# myReaderB.net
KiCad netlist of a schematic drawn in EAGLE
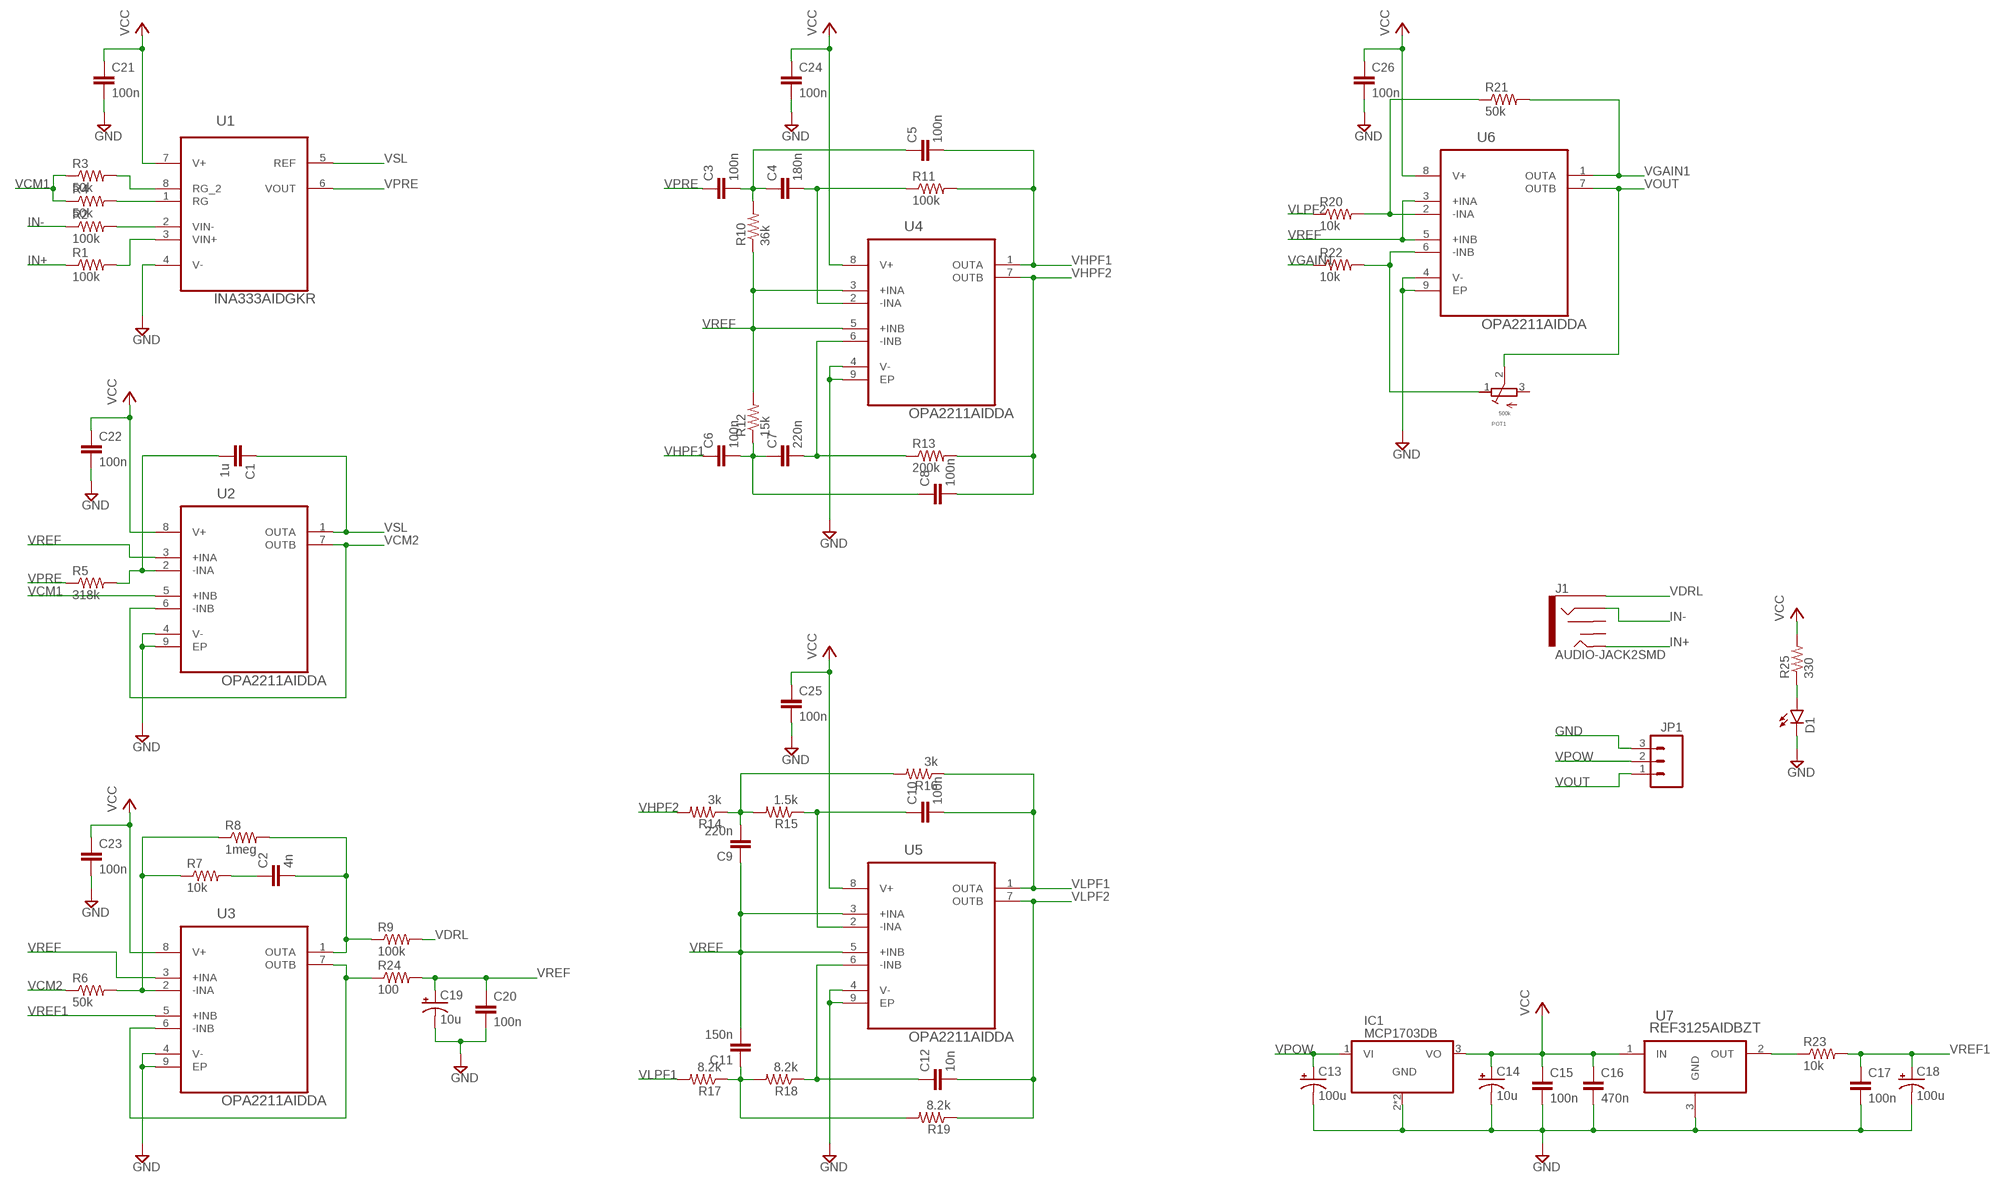
[diagram p0: schematic, sheet 1]

(export (version "E")
  (design (tool "Eeschema 10.0.6"))
  (components
    (comp (ref "C1")
      (value "1u")
      (footprint "eagle-import:0402-CAP")
      (libsource (lib "eagle-import") (part "CAP0402-CAP"))
    )
    (comp (ref "C2")
      (value "4n")
      (footprint "eagle-import:0402-CAP")
      (libsource (lib "eagle-import") (part "CAP0402-CAP"))
    )
    (comp (ref "C3")
      (value "100n")
      (footprint "eagle-import:0402-CAP")
      (libsource (lib "eagle-import") (part "CAP0402-CAP"))
    )
    (comp (ref "C4")
      (value "180n")
      (footprint "eagle-import:0402-CAP")
      (libsource (lib "eagle-import") (part "CAP0402-CAP"))
    )
    (comp (ref "C5")
      (value "100n")
      (footprint "eagle-import:0402-CAP")
      (libsource (lib "eagle-import") (part "CAP0402-CAP"))
    )
    (comp (ref "C6")
      (value "100n")
      (footprint "eagle-import:0402-CAP")
      (libsource (lib "eagle-import") (part "CAP0402-CAP"))
    )
    (comp (ref "C7")
      (value "220n")
      (footprint "eagle-import:0402-CAP")
      (libsource (lib "eagle-import") (part "CAP0402-CAP"))
    )
    (comp (ref "C8")
      (value "100n")
      (footprint "eagle-import:0402-CAP")
      (libsource (lib "eagle-import") (part "CAP0402-CAP"))
    )
    (comp (ref "C9")
      (value "220n")
      (footprint "eagle-import:0402-CAP")
      (libsource (lib "eagle-import") (part "CAP0402-CAP"))
    )
    (comp (ref "C10")
      (value "100n")
      (footprint "eagle-import:0402-CAP")
      (libsource (lib "eagle-import") (part "CAP0402-CAP"))
    )
    (comp (ref "C11")
      (value "150n")
      (footprint "eagle-import:0402-CAP")
      (libsource (lib "eagle-import") (part "CAP0402-CAP"))
    )
    (comp (ref "C12")
      (value "10n")
      (footprint "eagle-import:0402-CAP")
      (libsource (lib "eagle-import") (part "CAP0402-CAP"))
    )
    (comp (ref "C13")
      (value "100u")
      (footprint "eagle-import:EIA3216")
      (libsource (lib "eagle-import") (part "CAP_POL1206"))
    )
    (comp (ref "C14")
      (value "10u")
      (footprint "eagle-import:EIA3216")
      (libsource (lib "eagle-import") (part "CAP_POL1206"))
    )
    (comp (ref "C15")
      (value "100n")
      (footprint "eagle-import:0402-CAP")
      (libsource (lib "eagle-import") (part "CAP0402-CAP"))
    )
    (comp (ref "C16")
      (value "470n")
      (footprint "eagle-import:0402-CAP")
      (libsource (lib "eagle-import") (part "CAP0402-CAP"))
    )
    (comp (ref "C17")
      (value "100n")
      (footprint "eagle-import:0402-CAP")
      (libsource (lib "eagle-import") (part "CAP0402-CAP"))
    )
    (comp (ref "C18")
      (value "100u")
      (footprint "eagle-import:EIA3216")
      (libsource (lib "eagle-import") (part "CAP_POL1206"))
    )
    (comp (ref "C19")
      (value "10u")
      (footprint "eagle-import:EIA3216")
      (libsource (lib "eagle-import") (part "CAP_POL1206"))
    )
    (comp (ref "C20")
      (value "100n")
      (footprint "eagle-import:0402-CAP")
      (libsource (lib "eagle-import") (part "CAP0402-CAP"))
    )
    (comp (ref "C21")
      (value "100n")
      (footprint "eagle-import:0402-CAP")
      (libsource (lib "eagle-import") (part "CAP0402-CAP"))
    )
    (comp (ref "C22")
      (value "100n")
      (footprint "eagle-import:0402-CAP")
      (libsource (lib "eagle-import") (part "CAP0402-CAP"))
    )
    (comp (ref "C23")
      (value "100n")
      (footprint "eagle-import:0402-CAP")
      (libsource (lib "eagle-import") (part "CAP0402-CAP"))
    )
    (comp (ref "C24")
      (value "100n")
      (footprint "eagle-import:0402-CAP")
      (libsource (lib "eagle-import") (part "CAP0402-CAP"))
    )
    (comp (ref "C25")
      (value "100n")
      (footprint "eagle-import:0402-CAP")
      (libsource (lib "eagle-import") (part "CAP0402-CAP"))
    )
    (comp (ref "C26")
      (value "100n")
      (footprint "eagle-import:0402-CAP")
      (libsource (lib "eagle-import") (part "CAP0402-CAP"))
    )
    (comp (ref "D1")
      (value "LED0603")
      (footprint "eagle-import:LED-0603")
      (libsource (lib "eagle-import") (part "LED0603"))
    )
    (comp (ref "IC1")
      (value "MCP1703DB")
      (footprint "eagle-import:SOT223")
      (libsource (lib "eagle-import") (part "MCP1703DB"))
    )
    (comp (ref "J1")
      (value "AUDIO-JACK2SMD")
      (footprint "eagle-import:AUDIO-JACK-3.5MM-SMD")
      (libsource (lib "eagle-import") (part "AUDIO-JACK2SMD"))
    )
    (comp (ref "JP1")
      (value "M03PTH")
      (footprint "eagle-import:1X03")
      (libsource (lib "eagle-import") (part "M03PTH"))
    )
    (comp (ref "POT1")
      (value "500k")
      (footprint "eagle-import:BOURN_SMD_POTENTIOMETER")
      (libsource (lib "eagle-import") (part "BOURN_SMD_POTENTIOMETER2.1X2.7MMPACKAGE"))
    )
    (comp (ref "R1")
      (value "100k")
      (footprint "eagle-import:0402-RES")
      (libsource (lib "eagle-import") (part "RESISTOR0402-RES"))
    )
    (comp (ref "R2")
      (value "100k")
      (footprint "eagle-import:0402-RES")
      (libsource (lib "eagle-import") (part "RESISTOR0402-RES"))
    )
    (comp (ref "R3")
      (value "50k")
      (footprint "eagle-import:0402-RES")
      (libsource (lib "eagle-import") (part "RESISTOR0402-RES"))
    )
    (comp (ref "R4")
      (value "50k")
      (footprint "eagle-import:0402-RES")
      (libsource (lib "eagle-import") (part "RESISTOR0402-RES"))
    )
    (comp (ref "R5")
      (value "318k")
      (footprint "eagle-import:0402-RES")
      (libsource (lib "eagle-import") (part "RESISTOR0402-RES"))
    )
    (comp (ref "R6")
      (value "50k")
      (footprint "eagle-import:0402-RES")
      (libsource (lib "eagle-import") (part "RESISTOR0402-RES"))
    )
    (comp (ref "R7")
      (value "10k")
      (footprint "eagle-import:0402-RES")
      (libsource (lib "eagle-import") (part "RESISTOR0402-RES"))
    )
    (comp (ref "R8")
      (value "1meg")
      (footprint "eagle-import:0402-RES")
      (libsource (lib "eagle-import") (part "RESISTOR0402-RES"))
    )
    (comp (ref "R9")
      (value "100k")
      (footprint "eagle-import:0402-RES")
      (libsource (lib "eagle-import") (part "RESISTOR0402-RES"))
    )
    (comp (ref "R10")
      (value "36k")
      (footprint "eagle-import:0402-RES")
      (libsource (lib "eagle-import") (part "RESISTOR0402-RES"))
    )
    (comp (ref "R11")
      (value "100k")
      (footprint "eagle-import:0402-RES")
      (libsource (lib "eagle-import") (part "RESISTOR0402-RES"))
    )
    (comp (ref "R12")
      (value "15k")
      (footprint "eagle-import:0402-RES")
      (libsource (lib "eagle-import") (part "RESISTOR0402-RES"))
    )
    (comp (ref "R13")
      (value "200k")
      (footprint "eagle-import:0402-RES")
      (libsource (lib "eagle-import") (part "RESISTOR0402-RES"))
    )
    (comp (ref "R14")
      (value "3k")
      (footprint "eagle-import:0402-RES")
      (libsource (lib "eagle-import") (part "RESISTOR0402-RES"))
    )
    (comp (ref "R15")
      (value "1.5k")
      (footprint "eagle-import:0402-RES")
      (libsource (lib "eagle-import") (part "RESISTOR0402-RES"))
    )
    (comp (ref "R16")
      (value "3k")
      (footprint "eagle-import:0402-RES")
      (libsource (lib "eagle-import") (part "RESISTOR0402-RES"))
    )
    (comp (ref "R17")
      (value "8.2k")
      (footprint "eagle-import:0402-RES")
      (libsource (lib "eagle-import") (part "RESISTOR0402-RES"))
    )
    (comp (ref "R18")
      (value "8.2k")
      (footprint "eagle-import:0402-RES")
      (libsource (lib "eagle-import") (part "RESISTOR0402-RES"))
    )
    (comp (ref "R19")
      (value "8.2k")
      (footprint "eagle-import:0402-RES")
      (libsource (lib "eagle-import") (part "RESISTOR0402-RES"))
    )
    (comp (ref "R20")
      (value "10k")
      (footprint "eagle-import:0402-RES")
      (libsource (lib "eagle-import") (part "RESISTOR0402-RES"))
    )
    (comp (ref "R21")
      (value "50k")
      (footprint "eagle-import:0402-RES")
      (libsource (lib "eagle-import") (part "RESISTOR0402-RES"))
    )
    (comp (ref "R22")
      (value "10k")
      (footprint "eagle-import:0402-RES")
      (libsource (lib "eagle-import") (part "RESISTOR0402-RES"))
    )
    (comp (ref "R23")
      (value "10k")
      (footprint "eagle-import:0402-RES")
      (libsource (lib "eagle-import") (part "RESISTOR0402-RES"))
    )
    (comp (ref "R24")
      (value "100")
      (footprint "eagle-import:0402-RES")
      (libsource (lib "eagle-import") (part "RESISTOR0402-RES"))
    )
    (comp (ref "R25")
      (value "330")
      (footprint "eagle-import:0402-RES")
      (libsource (lib "eagle-import") (part "RESISTOR0402-RES"))
    )
    (comp (ref "U1")
      (value "INA333AIDGKR")
      (footprint "eagle-import:SOP65P490X110-8N")
      (libsource (lib "eagle-import") (part "INA333AIDGKR"))
    )
    (comp (ref "U2")
      (value "OPA2211AIDDA")
      (footprint "eagle-import:SOIC127P600X170-9N")
      (libsource (lib "eagle-import") (part "OPA2211AIDDA"))
    )
    (comp (ref "U3")
      (value "OPA2211AIDDA")
      (footprint "eagle-import:SOIC127P600X170-9N")
      (libsource (lib "eagle-import") (part "OPA2211AIDDA"))
    )
    (comp (ref "U4")
      (value "OPA2211AIDDA")
      (footprint "eagle-import:SOIC127P600X170-9N")
      (libsource (lib "eagle-import") (part "OPA2211AIDDA"))
    )
    (comp (ref "U5")
      (value "OPA2211AIDDA")
      (footprint "eagle-import:SOIC127P600X170-9N")
      (libsource (lib "eagle-import") (part "OPA2211AIDDA"))
    )
    (comp (ref "U6")
      (value "OPA2211AIDDA")
      (footprint "eagle-import:SOIC127P600X170-9N")
      (libsource (lib "eagle-import") (part "OPA2211AIDDA"))
    )
    (comp (ref "U7")
      (value "REF3125AIDBZT")
      (footprint "eagle-import:SOT95P237X112-3N")
      (libsource (lib "eagle-import") (part "REF3125AIDBZT"))
    )
  )
  (nets
    (net (code "1") (name "/IN+") (class "Default")
      (node (ref "J1") (pin "TIP") (pinfunction "TIP_TIP") (pintype "bidirectional"))
      (node (ref "R1") (pin "1") (pinfunction "1_1") (pintype "passive"))
    )
    (net (code "2") (name "/IN-") (class "Default")
      (node (ref "J1") (pin "RING") (pinfunction "RING_RING") (pintype "bidirectional"))
      (node (ref "R2") (pin "1") (pinfunction "1_1") (pintype "passive"))
    )
    (net (code "3") (name "/VCM1") (class "Default")
      (node (ref "R3") (pin "1") (pinfunction "1_1") (pintype "passive"))
      (node (ref "R4") (pin "1") (pinfunction "1_1") (pintype "passive"))
      (node (ref "U2") (pin "5") (pinfunction "+INB_5") (pintype "input"))
    )
    (net (code "4") (name "/VCM2") (class "Default")
      (node (ref "R6") (pin "1") (pinfunction "1_1") (pintype "passive"))
      (node (ref "U2") (pin "6") (pinfunction "-INB_6") (pintype "input"))
      (node (ref "U2") (pin "7") (pinfunction "OUTB_7") (pintype "output"))
    )
    (net (code "5") (name "/VDRL") (class "Default")
      (node (ref "J1") (pin "SLEEVE") (pinfunction "SLEEVE_SLEEVE") (pintype "bidirectional"))
      (node (ref "R9") (pin "2") (pinfunction "2_2") (pintype "passive"))
    )
    (net (code "6") (name "/VGAIN1") (class "Default")
      (node (ref "R21") (pin "2") (pinfunction "2_2") (pintype "passive"))
      (node (ref "R22") (pin "1") (pinfunction "1_1") (pintype "passive"))
      (node (ref "U6") (pin "1") (pinfunction "OUTA_1") (pintype "output"))
    )
    (net (code "7") (name "/VHPF1") (class "Default")
      (node (ref "C5") (pin "2") (pinfunction "2_2") (pintype "passive"))
      (node (ref "C6") (pin "1") (pinfunction "1_1") (pintype "passive"))
      (node (ref "R11") (pin "2") (pinfunction "2_2") (pintype "passive"))
      (node (ref "U4") (pin "1") (pinfunction "OUTA_1") (pintype "output"))
    )
    (net (code "8") (name "/VHPF2") (class "Default")
      (node (ref "C8") (pin "2") (pinfunction "2_2") (pintype "passive"))
      (node (ref "R13") (pin "2") (pinfunction "2_2") (pintype "passive"))
      (node (ref "R14") (pin "2") (pinfunction "2_2") (pintype "passive"))
      (node (ref "U4") (pin "7") (pinfunction "OUTB_7") (pintype "output"))
    )
    (net (code "9") (name "/VLPF1") (class "Default")
      (node (ref "C10") (pin "2") (pinfunction "2_2") (pintype "passive"))
      (node (ref "R16") (pin "1") (pinfunction "1_1") (pintype "passive"))
      (node (ref "R17") (pin "2") (pinfunction "2_2") (pintype "passive"))
      (node (ref "U5") (pin "1") (pinfunction "OUTA_1") (pintype "output"))
    )
    (net (code "10") (name "/VLPF2") (class "Default")
      (node (ref "C12") (pin "2") (pinfunction "2_2") (pintype "passive"))
      (node (ref "R19") (pin "1") (pinfunction "1_1") (pintype "passive"))
      (node (ref "R20") (pin "1") (pinfunction "1_1") (pintype "passive"))
      (node (ref "U5") (pin "7") (pinfunction "OUTB_7") (pintype "output"))
    )
    (net (code "11") (name "/VOUT") (class "Default")
      (node (ref "JP1") (pin "1") (pinfunction "1_1") (pintype "passive"))
      (node (ref "POT1") (pin "2") (pinfunction "S_2") (pintype "passive"))
      (node (ref "U6") (pin "7") (pinfunction "OUTB_7") (pintype "output"))
    )
    (net (code "12") (name "/VPOW") (class "Default")
      (node (ref "C13") (pin "A") (pinfunction "+_A") (pintype "passive"))
      (node (ref "IC1") (pin "1") (pinfunction "VI_1") (pintype "input"))
      (node (ref "JP1") (pin "2") (pinfunction "2_2") (pintype "passive"))
    )
    (net (code "13") (name "/VPRE") (class "Default")
      (node (ref "C3") (pin "1") (pinfunction "1_1") (pintype "passive"))
      (node (ref "R5") (pin "1") (pinfunction "1_1") (pintype "passive"))
      (node (ref "U1") (pin "6") (pinfunction "VOUT_6") (pintype "output"))
    )
    (net (code "14") (name "/VREF") (class "Default")
      (node (ref "C11") (pin "2") (pinfunction "2_2") (pintype "passive"))
      (node (ref "C19") (pin "A") (pinfunction "+_A") (pintype "passive"))
      (node (ref "C20") (pin "1") (pinfunction "1_1") (pintype "passive"))
      (node (ref "C9") (pin "1") (pinfunction "1_1") (pintype "passive"))
      (node (ref "R10") (pin "1") (pinfunction "1_1") (pintype "passive"))
      (node (ref "R12") (pin "2") (pinfunction "2_2") (pintype "passive"))
      (node (ref "R24") (pin "2") (pinfunction "2_2") (pintype "passive"))
      (node (ref "U2") (pin "3") (pinfunction "+INA_3") (pintype "input"))
      (node (ref "U3") (pin "3") (pinfunction "+INA_3") (pintype "input"))
      (node (ref "U4") (pin "3") (pinfunction "+INA_3") (pintype "input"))
      (node (ref "U4") (pin "5") (pinfunction "+INB_5") (pintype "input"))
      (node (ref "U5") (pin "3") (pinfunction "+INA_3") (pintype "input"))
      (node (ref "U5") (pin "5") (pinfunction "+INB_5") (pintype "input"))
      (node (ref "U6") (pin "3") (pinfunction "+INA_3") (pintype "input"))
      (node (ref "U6") (pin "5") (pinfunction "+INB_5") (pintype "input"))
    )
    (net (code "15") (name "/VREF1") (class "Default")
      (node (ref "C17") (pin "1") (pinfunction "1_1") (pintype "passive"))
      (node (ref "C18") (pin "A") (pinfunction "+_A") (pintype "passive"))
      (node (ref "R23") (pin "2") (pinfunction "2_2") (pintype "passive"))
      (node (ref "U3") (pin "5") (pinfunction "+INB_5") (pintype "input"))
    )
    (net (code "16") (name "/VSL") (class "Default")
      (node (ref "C1") (pin "1") (pinfunction "1_1") (pintype "passive"))
      (node (ref "U1") (pin "5") (pinfunction "REF_5") (pintype "output"))
      (node (ref "U2") (pin "1") (pinfunction "OUTA_1") (pintype "output"))
    )
    (net (code "17") (name "GND") (class "Default")
      (node (ref "C13") (pin "C") (pinfunction "-_C") (pintype "passive"))
      (node (ref "C14") (pin "C") (pinfunction "-_C") (pintype "passive"))
      (node (ref "C15") (pin "2") (pinfunction "2_2") (pintype "passive"))
      (node (ref "C16") (pin "2") (pinfunction "2_2") (pintype "passive"))
      (node (ref "C17") (pin "2") (pinfunction "2_2") (pintype "passive"))
      (node (ref "C18") (pin "C") (pinfunction "-_C") (pintype "passive"))
      (node (ref "C19") (pin "C") (pinfunction "-_C") (pintype "passive"))
      (node (ref "C20") (pin "2") (pinfunction "2_2") (pintype "passive"))
      (node (ref "C21") (pin "2") (pinfunction "2_2") (pintype "passive"))
      (node (ref "C22") (pin "2") (pinfunction "2_2") (pintype "passive"))
      (node (ref "C23") (pin "2") (pinfunction "2_2") (pintype "passive"))
      (node (ref "C24") (pin "2") (pinfunction "2_2") (pintype "passive"))
      (node (ref "C25") (pin "2") (pinfunction "2_2") (pintype "passive"))
      (node (ref "C26") (pin "2") (pinfunction "2_2") (pintype "passive"))
      (node (ref "D1") (pin "C") (pinfunction "C_C") (pintype "passive"))
      (node (ref "IC1") (pin "2") (pinfunction "GND_2") (pintype "passive"))
      (node (ref "IC1") (pin "4") (pinfunction "GND_4") (pintype "passive"))
      (node (ref "JP1") (pin "3") (pinfunction "3_3") (pintype "passive"))
      (node (ref "U1") (pin "4") (pinfunction "V-_4") (pintype "power_in"))
      (node (ref "U2") (pin "4") (pinfunction "V-_4") (pintype "power_in"))
      (node (ref "U2") (pin "9") (pinfunction "EP_9") (pintype "power_in"))
      (node (ref "U3") (pin "4") (pinfunction "V-_4") (pintype "power_in"))
      (node (ref "U3") (pin "9") (pinfunction "EP_9") (pintype "power_in"))
      (node (ref "U4") (pin "4") (pinfunction "V-_4") (pintype "power_in"))
      (node (ref "U4") (pin "9") (pinfunction "EP_9") (pintype "power_in"))
      (node (ref "U5") (pin "4") (pinfunction "V-_4") (pintype "power_in"))
      (node (ref "U5") (pin "9") (pinfunction "EP_9") (pintype "power_in"))
      (node (ref "U6") (pin "4") (pinfunction "V-_4") (pintype "power_in"))
      (node (ref "U6") (pin "9") (pinfunction "EP_9") (pintype "power_in"))
      (node (ref "U7") (pin "3") (pinfunction "GND_3") (pintype "passive"))
    )
    (net (code "18") (name "Net-(C2-Pad1)") (class "Default")
      (node (ref "C2") (pin "1") (pinfunction "1_1") (pintype "passive"))
      (node (ref "R7") (pin "2") (pinfunction "2_2") (pintype "passive"))
    )
    (net (code "19") (name "Net-(C3-Pad2)") (class "Default")
      (node (ref "C3") (pin "2") (pinfunction "2_2") (pintype "passive"))
      (node (ref "C4") (pin "1") (pinfunction "1_1") (pintype "passive"))
      (node (ref "C5") (pin "1") (pinfunction "1_1") (pintype "passive"))
      (node (ref "R10") (pin "2") (pinfunction "2_2") (pintype "passive"))
    )
    (net (code "20") (name "Net-(C6-Pad2)") (class "Default")
      (node (ref "C6") (pin "2") (pinfunction "2_2") (pintype "passive"))
      (node (ref "C7") (pin "1") (pinfunction "1_1") (pintype "passive"))
      (node (ref "C8") (pin "1") (pinfunction "1_1") (pintype "passive"))
      (node (ref "R12") (pin "1") (pinfunction "1_1") (pintype "passive"))
    )
    (net (code "21") (name "Net-(C9-Pad2)") (class "Default")
      (node (ref "C9") (pin "2") (pinfunction "2_2") (pintype "passive"))
      (node (ref "R14") (pin "1") (pinfunction "1_1") (pintype "passive"))
      (node (ref "R15") (pin "2") (pinfunction "2_2") (pintype "passive"))
      (node (ref "R16") (pin "2") (pinfunction "2_2") (pintype "passive"))
    )
    (net (code "22") (name "Net-(C11-Pad1)") (class "Default")
      (node (ref "C11") (pin "1") (pinfunction "1_1") (pintype "passive"))
      (node (ref "R17") (pin "1") (pinfunction "1_1") (pintype "passive"))
      (node (ref "R18") (pin "2") (pinfunction "2_2") (pintype "passive"))
      (node (ref "R19") (pin "2") (pinfunction "2_2") (pintype "passive"))
    )
    (net (code "23") (name "Net-(D1-PadA)") (class "Default")
      (node (ref "D1") (pin "A") (pinfunction "A_A") (pintype "passive"))
      (node (ref "R25") (pin "1") (pinfunction "1_1") (pintype "passive"))
    )
    (net (code "24") (name "Net-(POT1-A)") (class "Default")
      (node (ref "POT1") (pin "1") (pinfunction "A_1") (pintype "passive"))
      (node (ref "R22") (pin "2") (pinfunction "2_2") (pintype "passive"))
      (node (ref "U6") (pin "6") (pinfunction "-INB_6") (pintype "input"))
    )
    (net (code "25") (name "Net-(U1-RG)") (class "Default")
      (node (ref "R4") (pin "2") (pinfunction "2_2") (pintype "passive"))
      (node (ref "U1") (pin "1") (pinfunction "RG_1") (pintype "input"))
    )
    (net (code "26") (name "Net-(U1-RG_2)") (class "Default")
      (node (ref "R3") (pin "2") (pinfunction "2_2") (pintype "passive"))
      (node (ref "U1") (pin "8") (pinfunction "RG_2_8") (pintype "input"))
    )
    (net (code "27") (name "Net-(U1-VIN+)") (class "Default")
      (node (ref "R1") (pin "2") (pinfunction "2_2") (pintype "passive"))
      (node (ref "U1") (pin "3") (pinfunction "VIN+_3") (pintype "input"))
    )
    (net (code "28") (name "Net-(U1-VIN-)") (class "Default")
      (node (ref "R2") (pin "2") (pinfunction "2_2") (pintype "passive"))
      (node (ref "U1") (pin "2") (pinfunction "VIN-_2") (pintype "input"))
    )
    (net (code "29") (name "Net-(U2--INA)") (class "Default")
      (node (ref "C1") (pin "2") (pinfunction "2_2") (pintype "passive"))
      (node (ref "R5") (pin "2") (pinfunction "2_2") (pintype "passive"))
      (node (ref "U2") (pin "2") (pinfunction "-INA_2") (pintype "input"))
    )
    (net (code "30") (name "Net-(U3--INA)") (class "Default")
      (node (ref "R6") (pin "2") (pinfunction "2_2") (pintype "passive"))
      (node (ref "R7") (pin "1") (pinfunction "1_1") (pintype "passive"))
      (node (ref "R8") (pin "1") (pinfunction "1_1") (pintype "passive"))
      (node (ref "U3") (pin "2") (pinfunction "-INA_2") (pintype "input"))
    )
    (net (code "31") (name "Net-(U3--INB)") (class "Default")
      (node (ref "R24") (pin "1") (pinfunction "1_1") (pintype "passive"))
      (node (ref "U3") (pin "6") (pinfunction "-INB_6") (pintype "input"))
      (node (ref "U3") (pin "7") (pinfunction "OUTB_7") (pintype "output"))
    )
    (net (code "32") (name "Net-(U3-OUTA)") (class "Default")
      (node (ref "C2") (pin "2") (pinfunction "2_2") (pintype "passive"))
      (node (ref "R8") (pin "2") (pinfunction "2_2") (pintype "passive"))
      (node (ref "R9") (pin "1") (pinfunction "1_1") (pintype "passive"))
      (node (ref "U3") (pin "1") (pinfunction "OUTA_1") (pintype "output"))
    )
    (net (code "33") (name "Net-(U4--INA)") (class "Default")
      (node (ref "C4") (pin "2") (pinfunction "2_2") (pintype "passive"))
      (node (ref "R11") (pin "1") (pinfunction "1_1") (pintype "passive"))
      (node (ref "U4") (pin "2") (pinfunction "-INA_2") (pintype "input"))
    )
    (net (code "34") (name "Net-(U4--INB)") (class "Default")
      (node (ref "C7") (pin "2") (pinfunction "2_2") (pintype "passive"))
      (node (ref "R13") (pin "1") (pinfunction "1_1") (pintype "passive"))
      (node (ref "U4") (pin "6") (pinfunction "-INB_6") (pintype "input"))
    )
    (net (code "35") (name "Net-(U5--INA)") (class "Default")
      (node (ref "C10") (pin "1") (pinfunction "1_1") (pintype "passive"))
      (node (ref "R15") (pin "1") (pinfunction "1_1") (pintype "passive"))
      (node (ref "U5") (pin "2") (pinfunction "-INA_2") (pintype "input"))
    )
    (net (code "36") (name "Net-(U5--INB)") (class "Default")
      (node (ref "C12") (pin "1") (pinfunction "1_1") (pintype "passive"))
      (node (ref "R18") (pin "1") (pinfunction "1_1") (pintype "passive"))
      (node (ref "U5") (pin "6") (pinfunction "-INB_6") (pintype "input"))
    )
    (net (code "37") (name "Net-(U6--INA)") (class "Default")
      (node (ref "R20") (pin "2") (pinfunction "2_2") (pintype "passive"))
      (node (ref "R21") (pin "1") (pinfunction "1_1") (pintype "passive"))
      (node (ref "U6") (pin "2") (pinfunction "-INA_2") (pintype "input"))
    )
    (net (code "38") (name "Net-(U7-OUT)") (class "Default")
      (node (ref "R23") (pin "1") (pinfunction "1_1") (pintype "passive"))
      (node (ref "U7") (pin "2") (pinfunction "OUT_2") (pintype "output"))
    )
    (net (code "39") (name "VCC") (class "Default")
      (node (ref "C14") (pin "A") (pinfunction "+_A") (pintype "passive"))
      (node (ref "C15") (pin "1") (pinfunction "1_1") (pintype "passive"))
      (node (ref "C16") (pin "1") (pinfunction "1_1") (pintype "passive"))
      (node (ref "C21") (pin "1") (pinfunction "1_1") (pintype "passive"))
      (node (ref "C22") (pin "1") (pinfunction "1_1") (pintype "passive"))
      (node (ref "C23") (pin "1") (pinfunction "1_1") (pintype "passive"))
      (node (ref "C24") (pin "1") (pinfunction "1_1") (pintype "passive"))
      (node (ref "C25") (pin "1") (pinfunction "1_1") (pintype "passive"))
      (node (ref "C26") (pin "1") (pinfunction "1_1") (pintype "passive"))
      (node (ref "IC1") (pin "3") (pinfunction "VO_3") (pintype "passive"))
      (node (ref "R25") (pin "2") (pinfunction "2_2") (pintype "passive"))
      (node (ref "U1") (pin "7") (pinfunction "V+_7") (pintype "power_in"))
      (node (ref "U2") (pin "8") (pinfunction "V+_8") (pintype "power_in"))
      (node (ref "U3") (pin "8") (pinfunction "V+_8") (pintype "power_in"))
      (node (ref "U4") (pin "8") (pinfunction "V+_8") (pintype "power_in"))
      (node (ref "U5") (pin "8") (pinfunction "V+_8") (pintype "power_in"))
      (node (ref "U6") (pin "8") (pinfunction "V+_8") (pintype "power_in"))
      (node (ref "U7") (pin "1") (pinfunction "IN_1") (pintype "power_in"))
    )
    (net (code "40") (name "unconnected-(J1-PadRSH)") (class "Default")
      (node (ref "J1") (pin "RSH") (pinfunction "RSH_RSH") (pintype "bidirectional"))
    )
    (net (code "41") (name "unconnected-(J1-PadTSH)") (class "Default")
      (node (ref "J1") (pin "TSH") (pinfunction "TSH_TSH") (pintype "bidirectional"))
    )
    (net (code "42") (name "unconnected-(POT1-E-Pad3)") (class "Default")
      (node (ref "POT1") (pin "3") (pinfunction "E_3") (pintype "passive"))
    )
  )
)
